# Timer_Autoradio_NE555_CD4011.net
KiCad netlist of a schematic drawn in EAGLE
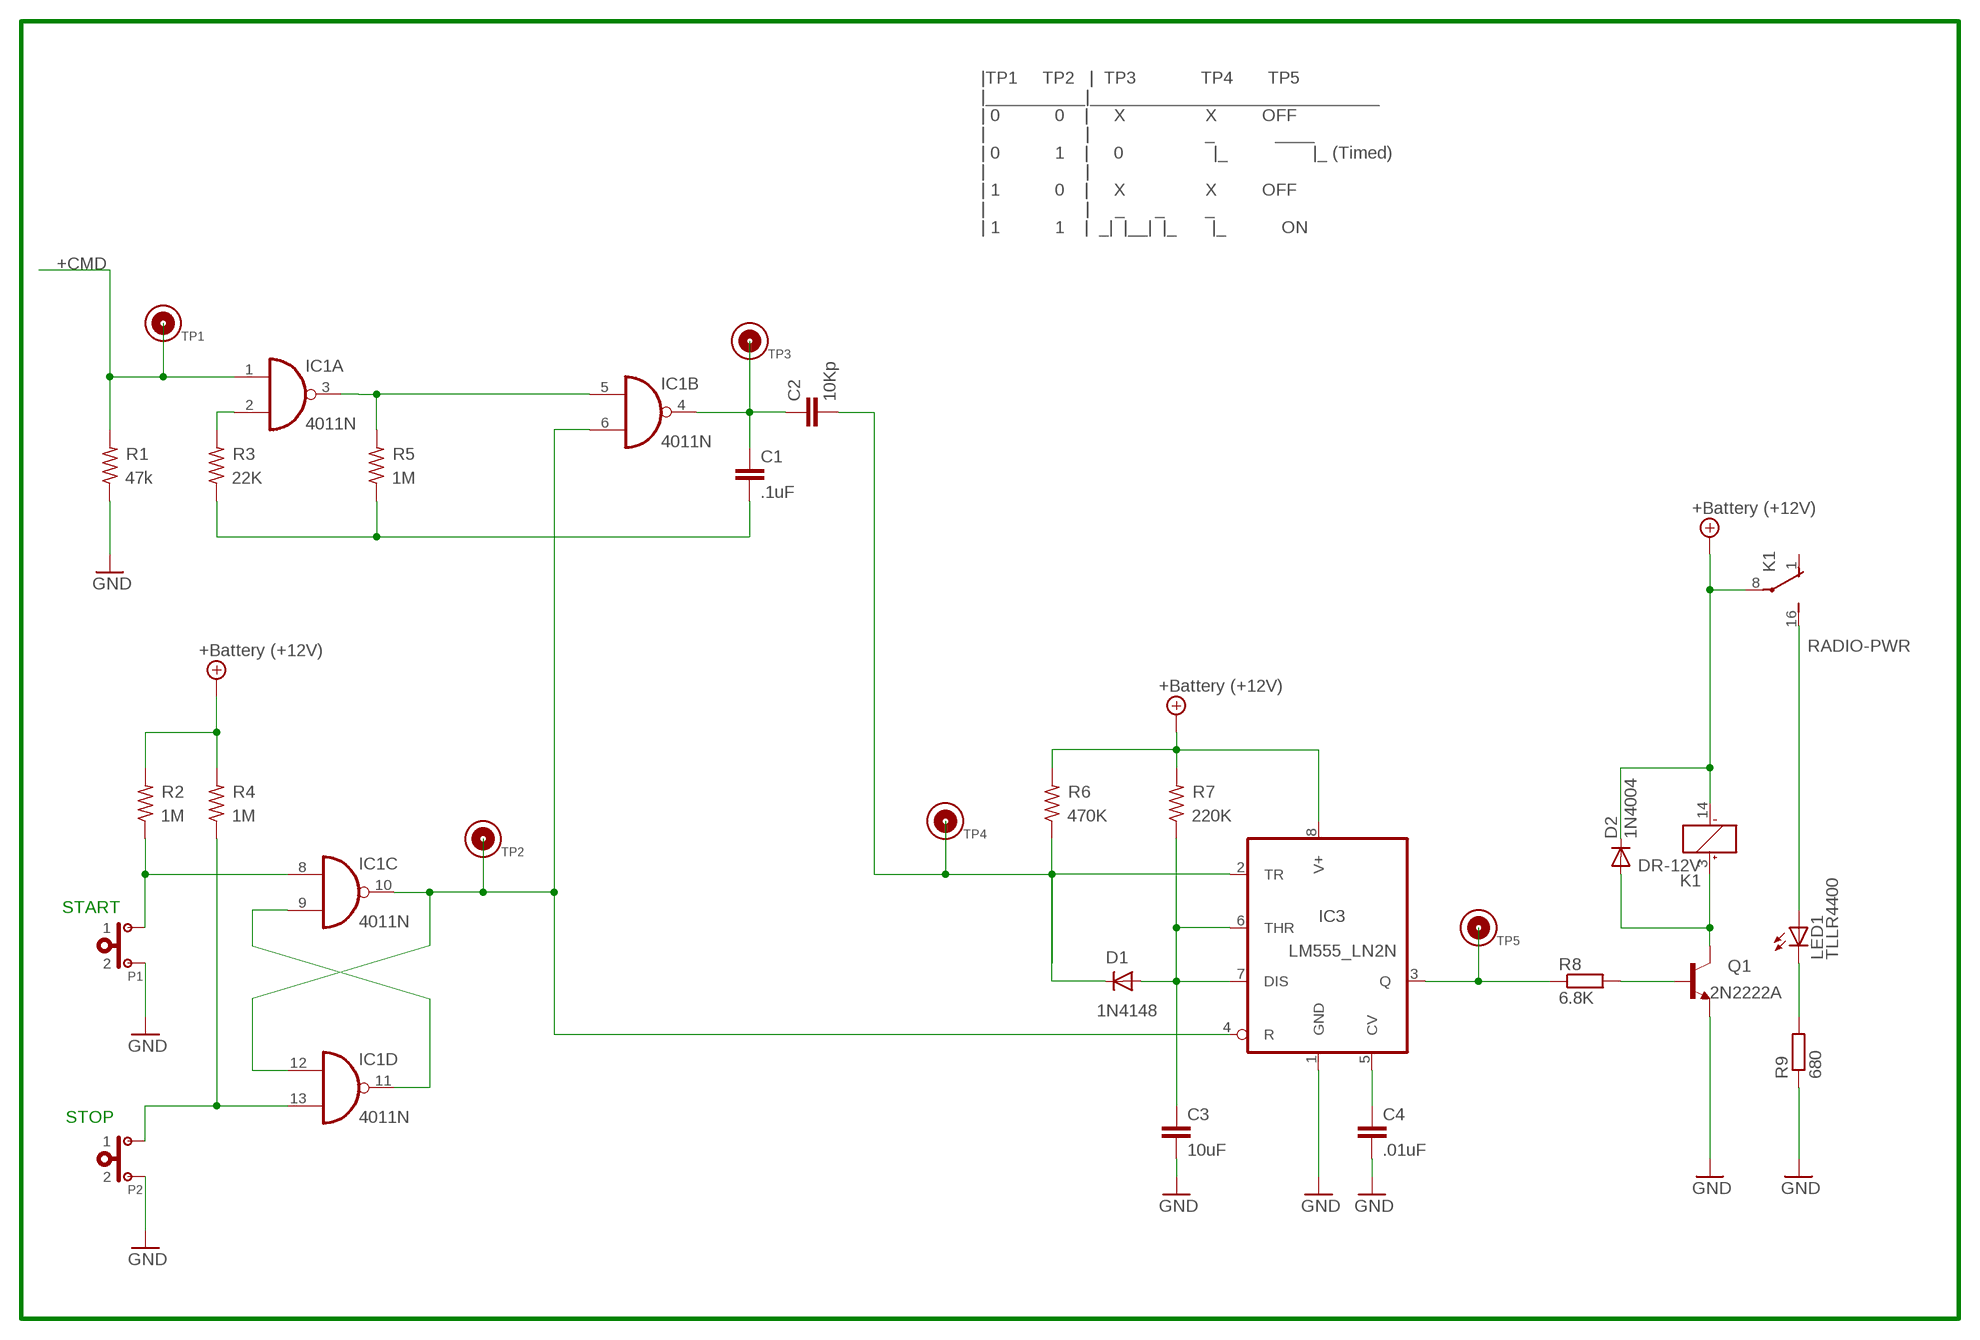
[diagram p0: schematic, sheet 1]

(export (version "E")
  (design (tool "Eeschema 10.0.6"))
  (components
    (comp (ref "C1")
      (value ".1uF")
      (footprint "eagle-import:C025-040X050")
      (libsource (lib "eagle-import") (part "C-EU025-040X050"))
    )
    (comp (ref "C2")
      (value "10Kp")
      (footprint "eagle-import:C025-040X050")
      (libsource (lib "eagle-import") (part "C-EU025-040X050"))
    )
    (comp (ref "C3")
      (value "10uF")
      (footprint "eagle-import:C025-040X050")
      (libsource (lib "eagle-import") (part "C-EU025-040X050"))
    )
    (comp (ref "C4")
      (value ".01uF")
      (footprint "eagle-import:C025-040X050")
      (libsource (lib "eagle-import") (part "C-EU025-040X050"))
    )
    (comp (ref "D1")
      (value "1N4148")
      (footprint "eagle-import:DO35-10")
      (libsource (lib "eagle-import") (part "1N4148DO35-10"))
    )
    (comp (ref "D2")
      (value "1N4004")
      (footprint "eagle-import:DO41-10")
      (libsource (lib "eagle-import") (part "1N4004"))
    )
    (comp (ref "IC1")
      (value "4011N")
      (footprint "eagle-import:DIL14")
      (libsource (lib "eagle-import") (part "4011N"))
    )
    (comp (ref "IC3")
      (value "LM555_LN2N")
      (footprint "eagle-import:DIL08")
      (libsource (lib "eagle-import") (part "555_LN2NLM"))
    )
    (comp (ref "K1")
      (value "DR-12V")
      (footprint "eagle-import:DR-1")
      (libsource (lib "eagle-import") (part "DR-V12"))
    )
    (comp (ref "LED1")
      (value "TLLR4400")
      (footprint "eagle-import:LED3MM")
      (fields (field (name "MF") "VISHAY SEMICONDUCTOR"))
      (libsource (lib "eagle-import") (part "TLLR4400"))
    )
    (comp (ref "P1")
      (value "PULSANTENO")
      (footprint "eagle-import:SIP02")
      (libsource (lib "eagle-import") (part "PULSANTENO"))
    )
    (comp (ref "P2")
      (value "PULSANTENO")
      (footprint "eagle-import:SIP02")
      (libsource (lib "eagle-import") (part "PULSANTENO"))
    )
    (comp (ref "Q1")
      (value "2N2222A")
      (footprint "eagle-import:TO18")
      (libsource (lib "eagle-import") (part "2N2222A"))
    )
    (comp (ref "R1")
      (value "47k")
      (footprint "eagle-import:0207_12")
      (libsource (lib "eagle-import") (part "R-US_0207/12"))
    )
    (comp (ref "R2")
      (value "1M")
      (footprint "eagle-import:0207_12")
      (libsource (lib "eagle-import") (part "R-US_0207/12"))
    )
    (comp (ref "R3")
      (value "22K")
      (footprint "eagle-import:0207_12")
      (libsource (lib "eagle-import") (part "R-US_0207/12"))
    )
    (comp (ref "R4")
      (value "1M")
      (footprint "eagle-import:0207_12")
      (libsource (lib "eagle-import") (part "R-US_0207/12"))
    )
    (comp (ref "R5")
      (value "1M")
      (footprint "eagle-import:0207_12")
      (libsource (lib "eagle-import") (part "R-US_0207/12"))
    )
    (comp (ref "R6")
      (value "470K")
      (footprint "eagle-import:0207_12")
      (libsource (lib "eagle-import") (part "R-US_0207/12"))
    )
    (comp (ref "R7")
      (value "220K")
      (footprint "eagle-import:0207_12")
      (libsource (lib "eagle-import") (part "R-US_0207/12"))
    )
    (comp (ref "R8")
      (value "6.8K")
      (footprint "eagle-import:0207_10")
      (libsource (lib "eagle-import") (part "R-EU_0207/10"))
    )
    (comp (ref "R9")
      (value "680")
      (footprint "eagle-import:0207_10")
      (libsource (lib "eagle-import") (part "R-EU_0207/10"))
    )
    (comp (ref "TP1")
      (value "SIP01")
      (footprint "eagle-import:SIP01")
      (libsource (lib "eagle-import") (part "SIP01"))
    )
    (comp (ref "TP2")
      (value "SIP01")
      (footprint "eagle-import:SIP01")
      (libsource (lib "eagle-import") (part "SIP01"))
    )
    (comp (ref "TP3")
      (value "SIP01")
      (footprint "eagle-import:SIP01")
      (libsource (lib "eagle-import") (part "SIP01"))
    )
    (comp (ref "TP4")
      (value "SIP01")
      (footprint "eagle-import:SIP01")
      (libsource (lib "eagle-import") (part "SIP01"))
    )
    (comp (ref "TP5")
      (value "SIP01")
      (footprint "eagle-import:SIP01")
      (libsource (lib "eagle-import") (part "SIP01"))
    )
  )
  (nets
    (net (code "1") (name "+Battery (+12V)") (class "Default")
      (node (ref "D2") (pin "C") (pinfunction "C_C") (pintype "passive"))
      (node (ref "IC3") (pin "8") (pinfunction "V+_8") (pintype "power_in"))
      (node (ref "K1") (pin "14") (pinfunction "-_14") (pintype "passive"))
      (node (ref "K1") (pin "8") (pinfunction "P_8") (pintype "passive"))
      (node (ref "R2") (pin "2") (pinfunction "2_2") (pintype "passive"))
      (node (ref "R4") (pin "2") (pinfunction "2_2") (pintype "passive"))
      (node (ref "R6") (pin "2") (pinfunction "2_2") (pintype "passive"))
      (node (ref "R7") (pin "2") (pinfunction "2_2") (pintype "passive"))
    )
    (net (code "2") (name "/+CMD") (class "Default")
      (node (ref "IC1") (pin "1") (pinfunction "I0_1") (pintype "input"))
      (node (ref "R1") (pin "2") (pinfunction "2_2") (pintype "passive"))
      (node (ref "TP1") (pin "P$1") (pinfunction "TP_P$1") (pintype "bidirectional"))
    )
    (net (code "3") (name "/RADIO-PWR") (class "Default")
      (node (ref "K1") (pin "16") (pinfunction "S_16") (pintype "passive"))
      (node (ref "LED1") (pin "A") (pinfunction "A_A") (pintype "passive"))
    )
    (net (code "4") (name "GND") (class "Default")
      (node (ref "C3") (pin "2") (pinfunction "2_2") (pintype "passive"))
      (node (ref "C4") (pin "2") (pinfunction "2_2") (pintype "passive"))
      (node (ref "IC3") (pin "1") (pinfunction "GND_1") (pintype "power_in"))
      (node (ref "P1") (pin "2") (pinfunction "2_2") (pintype "bidirectional"))
      (node (ref "P2") (pin "2") (pinfunction "2_2") (pintype "bidirectional"))
      (node (ref "Q1") (pin "1") (pinfunction "E_1") (pintype "passive"))
      (node (ref "R1") (pin "1") (pinfunction "1_1") (pintype "passive"))
      (node (ref "R9") (pin "1") (pinfunction "1_1") (pintype "passive"))
    )
    (net (code "5") (name "Net-(C1-Pad2)") (class "Default")
      (node (ref "C1") (pin "2") (pinfunction "2_2") (pintype "passive"))
      (node (ref "R3") (pin "1") (pinfunction "1_1") (pintype "passive"))
      (node (ref "R5") (pin "1") (pinfunction "1_1") (pintype "passive"))
    )
    (net (code "6") (name "Net-(IC1A-I1)") (class "Default")
      (node (ref "IC1") (pin "2") (pinfunction "I1_2") (pintype "input"))
      (node (ref "R3") (pin "2") (pinfunction "2_2") (pintype "passive"))
    )
    (net (code "7") (name "Net-(IC1A-O)") (class "Default")
      (node (ref "IC1") (pin "3") (pinfunction "O_3") (pintype "output"))
      (node (ref "IC1") (pin "5") (pinfunction "I0_5") (pintype "input"))
      (node (ref "R5") (pin "2") (pinfunction "2_2") (pintype "passive"))
    )
    (net (code "8") (name "Net-(IC1B-I1)") (class "Default")
      (node (ref "IC1") (pin "10") (pinfunction "O_10") (pintype "output"))
      (node (ref "IC1") (pin "12") (pinfunction "I0_12") (pintype "input"))
      (node (ref "IC1") (pin "6") (pinfunction "I1_6") (pintype "input"))
      (node (ref "IC3") (pin "4") (pinfunction "R_4") (pintype "input"))
      (node (ref "TP2") (pin "P$1") (pinfunction "TP_P$1") (pintype "bidirectional"))
    )
    (net (code "9") (name "Net-(IC1B-O)") (class "Default")
      (node (ref "C1") (pin "1") (pinfunction "1_1") (pintype "passive"))
      (node (ref "C2") (pin "1") (pinfunction "1_1") (pintype "passive"))
      (node (ref "IC1") (pin "4") (pinfunction "O_4") (pintype "output"))
      (node (ref "TP3") (pin "P$1") (pinfunction "TP_P$1") (pintype "bidirectional"))
    )
    (net (code "10") (name "Net-(IC1C-I0)") (class "Default")
      (node (ref "IC1") (pin "8") (pinfunction "I0_8") (pintype "input"))
      (node (ref "P1") (pin "1") (pinfunction "1_1") (pintype "bidirectional"))
      (node (ref "R2") (pin "1") (pinfunction "1_1") (pintype "passive"))
    )
    (net (code "11") (name "Net-(IC1C-I1)") (class "Default")
      (node (ref "IC1") (pin "11") (pinfunction "O_11") (pintype "output"))
      (node (ref "IC1") (pin "9") (pinfunction "I1_9") (pintype "input"))
    )
    (net (code "12") (name "Net-(IC1D-I1)") (class "Default")
      (node (ref "IC1") (pin "13") (pinfunction "I1_13") (pintype "input"))
      (node (ref "P2") (pin "1") (pinfunction "1_1") (pintype "bidirectional"))
      (node (ref "R4") (pin "1") (pinfunction "1_1") (pintype "passive"))
    )
    (net (code "13") (name "Net-(IC3-CV)") (class "Default")
      (node (ref "C4") (pin "1") (pinfunction "1_1") (pintype "passive"))
      (node (ref "IC3") (pin "5") (pinfunction "CV_5") (pintype "input"))
    )
    (net (code "14") (name "Net-(IC3-DIS)") (class "Default")
      (node (ref "C3") (pin "1") (pinfunction "1_1") (pintype "passive"))
      (node (ref "D1") (pin "A") (pinfunction "A_A") (pintype "passive"))
      (node (ref "IC3") (pin "6") (pinfunction "THR_6") (pintype "input"))
      (node (ref "IC3") (pin "7") (pinfunction "DIS_7") (pintype "input"))
      (node (ref "R7") (pin "1") (pinfunction "1_1") (pintype "passive"))
    )
    (net (code "15") (name "Net-(IC3-Q)") (class "Default")
      (node (ref "IC3") (pin "3") (pinfunction "Q_3") (pintype "output"))
      (node (ref "R8") (pin "1") (pinfunction "1_1") (pintype "passive"))
      (node (ref "TP5") (pin "P$1") (pinfunction "TP_P$1") (pintype "bidirectional"))
    )
    (net (code "16") (name "Net-(IC3-TR)") (class "Default")
      (node (ref "C2") (pin "2") (pinfunction "2_2") (pintype "passive"))
      (node (ref "D1") (pin "C") (pinfunction "C_C") (pintype "passive"))
      (node (ref "IC3") (pin "2") (pinfunction "TR_2") (pintype "input"))
      (node (ref "R6") (pin "1") (pinfunction "1_1") (pintype "passive"))
      (node (ref "TP4") (pin "P$1") (pinfunction "TP_P$1") (pintype "bidirectional"))
    )
    (net (code "17") (name "Net-(K1A-+)") (class "Default")
      (node (ref "D2") (pin "A") (pinfunction "A_A") (pintype "passive"))
      (node (ref "K1") (pin "3") (pinfunction "+_3") (pintype "passive"))
      (node (ref "Q1") (pin "3") (pinfunction "C_3") (pintype "passive"))
    )
    (net (code "18") (name "Net-(LED1-C)") (class "Default")
      (node (ref "LED1") (pin "K") (pinfunction "C_K") (pintype "passive"))
      (node (ref "R9") (pin "2") (pinfunction "2_2") (pintype "passive"))
    )
    (net (code "19") (name "Net-(Q1-B)") (class "Default")
      (node (ref "Q1") (pin "2") (pinfunction "B_2") (pintype "passive"))
      (node (ref "R8") (pin "2") (pinfunction "2_2") (pintype "passive"))
    )
    (net (code "20") (name "unconnected-(K1B-O-Pad1)") (class "Default")
      (node (ref "K1") (pin "1") (pinfunction "O_1") (pintype "passive"))
    )
  )
)
